# FD_Capacitance_Sensor_v13.net
KiCad netlist of a schematic drawn in EAGLE
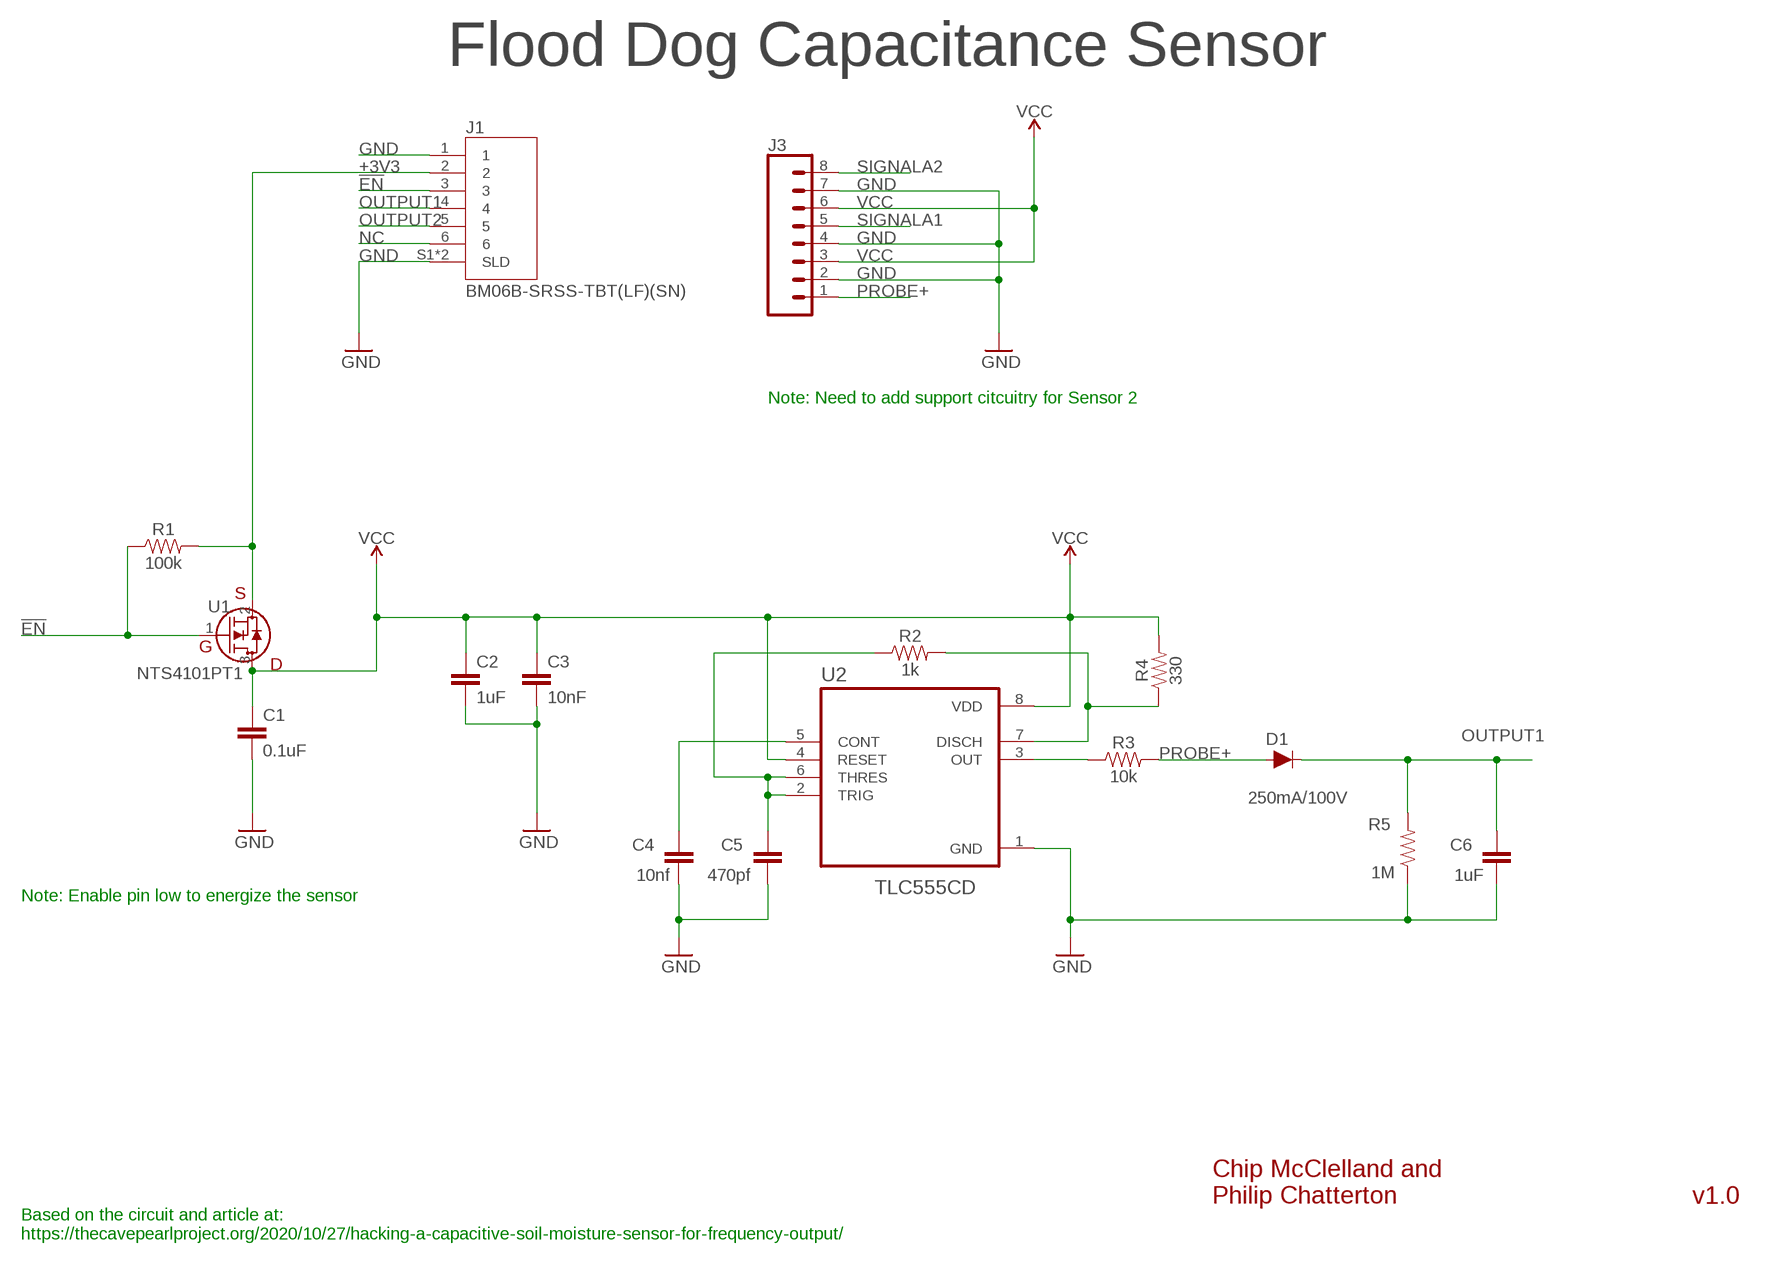
[diagram p0: schematic, sheet 1]

(export (version "E")
  (design (tool "Eeschema 10.0.6"))
  (components
    (comp (ref "C1")
      (value "0.1uF")
      (footprint "eagle-import:0805@1")
      (fields (field (name "HOUSEPART") "YES") (field (name "MPN") "MF-CAP-0805-0.1uF"))
      (libsource (lib "eagle-import") (part "CAP-MF-0.1UF-0805"))
    )
    (comp (ref "C2")
      (value "1uF")
      (footprint "eagle-import:0805@1")
      (fields (field (name "HOUSEPART") "yes") (field (name "MPN") "MF-CAP-0805-1uF"))
      (libsource (lib "eagle-import") (part "CAP-MF-1UF-0805"))
    )
    (comp (ref "C3")
      (value "10nF")
      (footprint "eagle-import:0805@1")
      (fields (field (name "HOUSEPART") "NO") (field (name "MPN") "C0805X103K1RAC3316"))
      (libsource (lib "eagle-import") (part "CAP-10NF-0805"))
    )
    (comp (ref "C4")
      (value "10nf")
      (footprint "eagle-import:C0805")
      (libsource (lib "eagle-import") (part "C-EUC0805"))
    )
    (comp (ref "C5")
      (value "470pf")
      (footprint "eagle-import:C0805")
      (libsource (lib "eagle-import") (part "C-EUC0805"))
    )
    (comp (ref "C6")
      (value "1uF")
      (footprint "eagle-import:C0805")
      (libsource (lib "eagle-import") (part "C-EUC0805"))
    )
    (comp (ref "D1")
      (value "250mA/100V")
      (footprint "eagle-import:SOD-323")
      (fields (field (name "MPN") "BAS16HT1G"))
      (libsource (lib "eagle-import") (part "DIODE-BAS16J"))
    )
    (comp (ref "J1")
      (value "BM06B-SRSS-TBT(LF)(SN)")
      (footprint "eagle-import:JST_BM06B-SRSS-TB(LF)(SN)")
      (libsource (lib "eagle-import") (part "BM06B-SRSS-TBT(LF)(SN)"))
    )
    (comp (ref "J3")
      (value "CONN_08\"")
      (footprint "eagle-import:1X08")
      (libsource (lib "eagle-import") (part "CONN_08{dblquote}"))
    )
    (comp (ref "R1")
      (value "100k")
      (footprint "eagle-import:0805")
      (fields (field (name "MPN") "MF-RES-0805-100K") (field (name "MPN_1") "MF-RES-0805-100K"))
      (libsource (lib "eagle-import") (part "RESISTOR-MF-100K-0805"))
    )
    (comp (ref "R2")
      (value "1k")
      (footprint "eagle-import:0805")
      (fields (field (name "HOUSEPART") "YES") (field (name "MPN") "MF-RES-0805-1K"))
      (libsource (lib "eagle-import") (part "RESISTOR-MF-1K-0805"))
    )
    (comp (ref "R3")
      (value "10k")
      (footprint "eagle-import:0805")
      (fields (field (name "MPN") "MF-RES-0805-10K"))
      (libsource (lib "eagle-import") (part "RESISTOR-MF-10K-0805"))
    )
    (comp (ref "R4")
      (value "330")
      (footprint "eagle-import:0805")
      (fields (field (name "HOUSEPART") "YES") (field (name "MPN") "MF-RES-0805-330"))
      (libsource (lib "eagle-import") (part "RESISTOR-MF-330-0805"))
    )
    (comp (ref "R5")
      (value "1M")
      (footprint "eagle-import:0805")
      (fields (field (name "HOUSEPART") "YES") (field (name "MPN") "MF-RES-0805-1K"))
      (libsource (lib "eagle-import") (part "RESISTOR-MF-1K-0805"))
    )
    (comp (ref "U1")
      (value "NTS4101PT1")
      (footprint "eagle-import:SOT_101PT1_ONS")
      (libsource (lib "eagle-import") (part "NTS4101PT1"))
    )
    (comp (ref "U2")
      (value "TLC555CD")
      (footprint "eagle-import:SOIC127P599X175-8N")
      (fields (field (name "DIGI-KEY_PART_NUMBER") "296-52992-ND") (field (name "MF") "Texas Instruments"))
      (libsource (lib "eagle-import") (part "TLC555CD"))
    )
  )
  (nets
    (net (code "1") (name "/+3V3") (class "Default")
      (node (ref "J1") (pin "2") (pinfunction "2_2") (pintype "passive"))
      (node (ref "R1") (pin "2") (pinfunction "2_2") (pintype "passive"))
      (node (ref "U1") (pin "2") (pinfunction "S_2") (pintype "passive"))
    )
    (net (code "2") (name "/NC") (class "Default")
      (node (ref "J1") (pin "6") (pinfunction "6_6") (pintype "passive"))
    )
    (net (code "3") (name "/OUTPUT1") (class "Default")
      (node (ref "C6") (pin "2") (pinfunction "2_2") (pintype "passive"))
      (node (ref "D1") (pin "C") (pinfunction "C_C") (pintype "passive"))
      (node (ref "J1") (pin "4") (pinfunction "4_4") (pintype "passive"))
      (node (ref "R5") (pin "2") (pinfunction "2_2") (pintype "passive"))
    )
    (net (code "4") (name "/OUTPUT2") (class "Default")
      (node (ref "J1") (pin "5") (pinfunction "5_5") (pintype "passive"))
    )
    (net (code "5") (name "/PROBE+") (class "Default")
      (node (ref "D1") (pin "A") (pinfunction "A_A") (pintype "passive"))
      (node (ref "J3") (pin "1") (pinfunction "1_1") (pintype "passive"))
      (node (ref "R3") (pin "2") (pinfunction "2_2") (pintype "passive"))
    )
    (net (code "6") (name "/SIGNALA1") (class "Default")
      (node (ref "J3") (pin "5") (pinfunction "5_5") (pintype "passive"))
    )
    (net (code "7") (name "/SIGNALA2") (class "Default")
      (node (ref "J3") (pin "8") (pinfunction "8_8") (pintype "passive"))
    )
    (net (code "8") (name "/~{EN}") (class "Default")
      (node (ref "J1") (pin "3") (pinfunction "3_3") (pintype "passive"))
      (node (ref "R1") (pin "1") (pinfunction "1_1") (pintype "passive"))
      (node (ref "U1") (pin "1") (pinfunction "G_1") (pintype "passive"))
    )
    (net (code "9") (name "GND") (class "Default")
      (node (ref "C1") (pin "2") (pinfunction "2_2") (pintype "passive"))
      (node (ref "C2") (pin "2") (pinfunction "2_2") (pintype "passive"))
      (node (ref "C3") (pin "2") (pinfunction "2_2") (pintype "passive"))
      (node (ref "C4") (pin "1") (pinfunction "1_1") (pintype "passive"))
      (node (ref "C5") (pin "1") (pinfunction "1_1") (pintype "passive"))
      (node (ref "C6") (pin "1") (pinfunction "1_1") (pintype "passive"))
      (node (ref "J1") (pin "1") (pinfunction "1_1") (pintype "passive"))
      (node (ref "J1") (pin "S1") (pinfunction "SLD_S1") (pintype "passive"))
      (node (ref "J1") (pin "S2") (pinfunction "SLD_S2") (pintype "passive"))
      (node (ref "J3") (pin "2") (pinfunction "2_2") (pintype "passive"))
      (node (ref "J3") (pin "4") (pinfunction "4_4") (pintype "passive"))
      (node (ref "J3") (pin "7") (pinfunction "7_7") (pintype "passive"))
      (node (ref "R5") (pin "1") (pinfunction "1_1") (pintype "passive"))
      (node (ref "U2") (pin "1") (pinfunction "GND_1") (pintype "power_in"))
    )
    (net (code "10") (name "Net-(U2-CONT)") (class "Default")
      (node (ref "C4") (pin "2") (pinfunction "2_2") (pintype "passive"))
      (node (ref "U2") (pin "5") (pinfunction "CONT_5") (pintype "input"))
    )
    (net (code "11") (name "Net-(U2-DISCH)") (class "Default")
      (node (ref "R2") (pin "2") (pinfunction "2_2") (pintype "passive"))
      (node (ref "R4") (pin "1") (pinfunction "1_1") (pintype "passive"))
      (node (ref "U2") (pin "7") (pinfunction "DISCH_7") (pintype "output"))
    )
    (net (code "12") (name "Net-(U2-OUT)") (class "Default")
      (node (ref "R3") (pin "1") (pinfunction "1_1") (pintype "passive"))
      (node (ref "U2") (pin "3") (pinfunction "OUT_3") (pintype "output"))
    )
    (net (code "13") (name "Net-(U2-THRES)") (class "Default")
      (node (ref "C5") (pin "2") (pinfunction "2_2") (pintype "passive"))
      (node (ref "R2") (pin "1") (pinfunction "1_1") (pintype "passive"))
      (node (ref "U2") (pin "2") (pinfunction "TRIG_2") (pintype "input"))
      (node (ref "U2") (pin "6") (pinfunction "THRES_6") (pintype "input"))
    )
    (net (code "14") (name "VCC") (class "Default")
      (node (ref "C1") (pin "1") (pinfunction "1_1") (pintype "passive"))
      (node (ref "C2") (pin "1") (pinfunction "1_1") (pintype "passive"))
      (node (ref "C3") (pin "1") (pinfunction "1_1") (pintype "passive"))
      (node (ref "J3") (pin "3") (pinfunction "3_3") (pintype "passive"))
      (node (ref "J3") (pin "6") (pinfunction "6_6") (pintype "passive"))
      (node (ref "R4") (pin "2") (pinfunction "2_2") (pintype "passive"))
      (node (ref "U1") (pin "3") (pinfunction "D_3") (pintype "passive"))
      (node (ref "U2") (pin "4") (pinfunction "RESET_4") (pintype "input"))
      (node (ref "U2") (pin "8") (pinfunction "VDD_8") (pintype "power_in"))
    )
  )
)
